# Aldi_Ambiano_Reflow_Oven_Main_Board.net
KiCad netlist of a schematic drawn in EAGLE
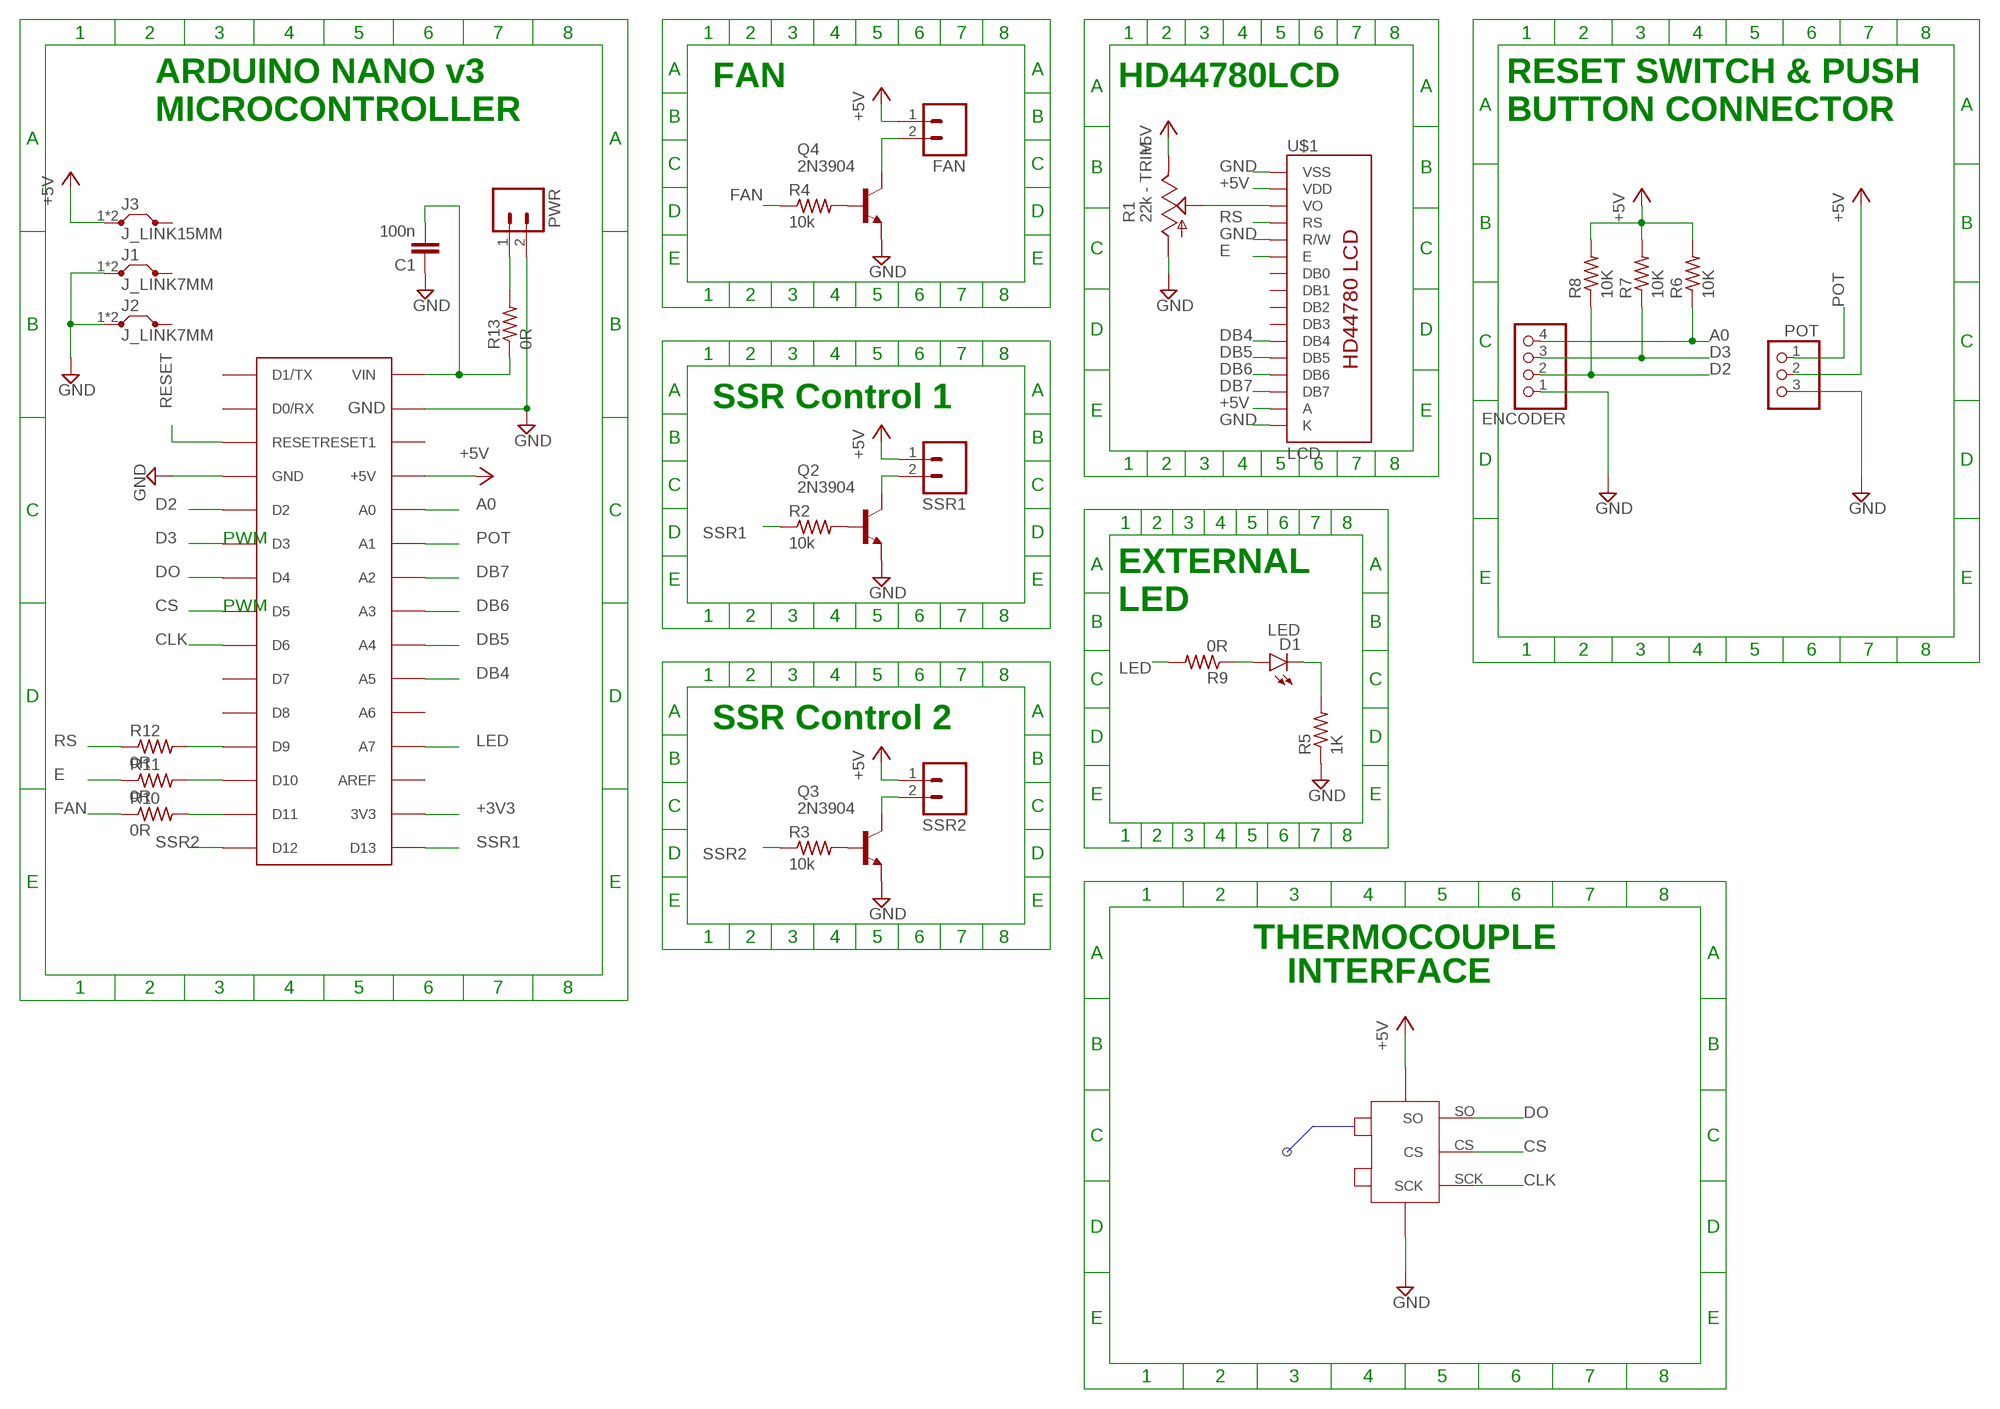
[diagram p0: schematic, sheet 1]

(export (version "E")
  (design (tool "Eeschema 10.0.6"))
  (components
    (comp (ref "ARDUINO")
      (value "Arduino Nano v3.0")
      (footprint "eagle-import:PDIP-32")
      (libsource (lib "eagle-import") (part "ARDUINONANO"))
    )
    (comp (ref "C1")
      (value "100n")
      (footprint "eagle-import:CAP-PTH-5MM")
      (libsource (lib "eagle-import") (part "CAPPTH1"))
    )
    (comp (ref "D1")
      (value "LED")
      (footprint "eagle-import:LED3MM")
      (libsource (lib "eagle-import") (part "LED3MM"))
    )
    (comp (ref "ENCODER")
      (value "PINHD-1X4/90")
      (footprint "eagle-import:1X04_90")
      (libsource (lib "eagle-import") (part "PINHD-1X4/90"))
    )
    (comp (ref "FAN")
      (value "M025MM")
      (footprint "eagle-import:SCREWTERMINAL-5MM-2")
      (libsource (lib "eagle-import") (part "M025MM"))
    )
    (comp (ref "J1")
      (value "J_LINK7MM")
      (footprint "eagle-import:07")
      (libsource (lib "eagle-import") (part "J_LINK7MM"))
    )
    (comp (ref "J2")
      (value "J_LINK7MM")
      (footprint "eagle-import:07")
      (libsource (lib "eagle-import") (part "J_LINK7MM"))
    )
    (comp (ref "J3")
      (value "J_LINK15MM")
      (footprint "eagle-import:15")
      (libsource (lib "eagle-import") (part "J_LINK15MM"))
    )
    (comp (ref "POT")
      (value "PINHD-1X3/90")
      (footprint "eagle-import:1X03_90")
      (libsource (lib "eagle-import") (part "PINHD-1X3/90"))
    )
    (comp (ref "PWR")
      (value "M025MM")
      (footprint "eagle-import:SCREWTERMINAL-5MM-2")
      (libsource (lib "eagle-import") (part "M025MM"))
    )
    (comp (ref "Q2")
      (value "2N3904")
      (footprint "eagle-import:TO92")
      (libsource (lib "eagle-import") (part "2N3904"))
    )
    (comp (ref "Q3")
      (value "2N3904")
      (footprint "eagle-import:TO92")
      (libsource (lib "eagle-import") (part "2N3904"))
    )
    (comp (ref "Q4")
      (value "2N3904")
      (footprint "eagle-import:TO92")
      (libsource (lib "eagle-import") (part "2N3904"))
    )
    (comp (ref "R1")
      (value "22k - TRIM")
      (footprint "eagle-import:CA9V")
      (libsource (lib "eagle-import") (part "TRIM_US-CA9V"))
    )
    (comp (ref "R2")
      (value "10k")
      (footprint "eagle-import:R0207_3")
      (libsource (lib "eagle-import") (part "6MM.3"))
    )
    (comp (ref "R3")
      (value "10k")
      (footprint "eagle-import:R0207_3")
      (libsource (lib "eagle-import") (part "6MM.3"))
    )
    (comp (ref "R4")
      (value "10k")
      (footprint "eagle-import:R0207_3")
      (libsource (lib "eagle-import") (part "6MM.3"))
    )
    (comp (ref "R5")
      (value "1K")
      (footprint "eagle-import:R0207_3")
      (libsource (lib "eagle-import") (part "6MM.3"))
    )
    (comp (ref "R6")
      (value "10K")
      (footprint "eagle-import:R0207_4")
      (libsource (lib "eagle-import") (part "6MM.4"))
    )
    (comp (ref "R7")
      (value "10K")
      (footprint "eagle-import:R0207_3")
      (libsource (lib "eagle-import") (part "6MM.3"))
    )
    (comp (ref "R8")
      (value "10K")
      (footprint "eagle-import:R0207_4")
      (libsource (lib "eagle-import") (part "6MM.4"))
    )
    (comp (ref "R9")
      (value "0R")
      (footprint "eagle-import:R0207_4")
      (libsource (lib "eagle-import") (part "6MM.4"))
    )
    (comp (ref "R10")
      (value "0R")
      (footprint "eagle-import:R0207_3")
      (libsource (lib "eagle-import") (part "6MM.3"))
    )
    (comp (ref "R11")
      (value "0R")
      (footprint "eagle-import:R0207_6")
      (libsource (lib "eagle-import") (part "6MM.6"))
    )
    (comp (ref "R12")
      (value "0R")
      (footprint "eagle-import:R0207_3")
      (libsource (lib "eagle-import") (part "6MM.3"))
    )
    (comp (ref "R13")
      (value "0R")
      (footprint "eagle-import:R0207_5")
      (libsource (lib "eagle-import") (part "6MM.5"))
    )
    (comp (ref "SSR1")
      (value "M025MM")
      (footprint "eagle-import:SCREWTERMINAL-5MM-2")
      (libsource (lib "eagle-import") (part "M025MM"))
    )
    (comp (ref "SSR2")
      (value "M025MM")
      (footprint "eagle-import:SCREWTERMINAL-5MM-2")
      (libsource (lib "eagle-import") (part "M025MM"))
    )
    (comp (ref "U$1")
      (value "LCD")
      (footprint "eagle-import:LCD-16X2-4HOLES")
      (libsource (lib "eagle-import") (part "LCD-HD4478016X2-4-HOLES4-HOLES"))
    )
    (comp (ref "U$2")
      (value "MAX6675_BREAKOUT")
      (footprint "eagle-import:MAX6675_BREAKOUT")
      (libsource (lib "eagle-import") (part "MAX6675_BREAKOUT"))
    )
  )
  (nets
    (net (code "1") (name "+5V") (class "Default")
      (node (ref "ARDUINO") (pin "+5V") (pinfunction "+5V_+5V") (pintype "bidirectional"))
      (node (ref "FAN") (pin "1") (pinfunction "1_1") (pintype "passive"))
      (node (ref "J3") (pin "1") (pinfunction "1_1") (pintype "passive"))
      (node (ref "J3") (pin "2") (pinfunction "1_2") (pintype "passive"))
      (node (ref "POT") (pin "2") (pinfunction "2_2") (pintype "passive"))
      (node (ref "R1") (pin "E") (pinfunction "E_E") (pintype "passive"))
      (node (ref "R6") (pin "2") (pinfunction "2_2") (pintype "passive"))
      (node (ref "R7") (pin "2") (pinfunction "2_2") (pintype "passive"))
      (node (ref "R8") (pin "2") (pinfunction "2_2") (pintype "passive"))
      (node (ref "SSR1") (pin "1") (pinfunction "1_1") (pintype "passive"))
      (node (ref "SSR2") (pin "1") (pinfunction "1_1") (pintype "passive"))
      (node (ref "U$1") (pin "15") (pinfunction "A_15") (pintype "power_in"))
      (node (ref "U$1") (pin "2") (pinfunction "VDD_2") (pintype "power_in"))
      (node (ref "U$2") (pin "VCC") (pinfunction "VCC_VCC") (pintype "power_in"))
    )
    (net (code "2") (name "/+3V3") (class "Default")
      (node (ref "ARDUINO") (pin "3V3") (pinfunction "3V3_3V3") (pintype "bidirectional"))
    )
    (net (code "3") (name "/A0") (class "Default")
      (node (ref "ARDUINO") (pin "A0") (pinfunction "A0_A0") (pintype "bidirectional"))
      (node (ref "ENCODER") (pin "4") (pinfunction "4_4") (pintype "passive"))
      (node (ref "R6") (pin "1") (pinfunction "1_1") (pintype "passive"))
    )
    (net (code "4") (name "/CLK") (class "Default")
      (node (ref "ARDUINO") (pin "D6") (pinfunction "D6_D6") (pintype "bidirectional"))
      (node (ref "U$2") (pin "SCK") (pinfunction "SCK_SCK") (pintype "bidirectional"))
    )
    (net (code "5") (name "/CS") (class "Default")
      (node (ref "ARDUINO") (pin "D5") (pinfunction "D5_D5") (pintype "bidirectional"))
      (node (ref "U$2") (pin "CS") (pinfunction "CS_CS") (pintype "bidirectional"))
    )
    (net (code "6") (name "/D2") (class "Default")
      (node (ref "ARDUINO") (pin "D2") (pinfunction "D2_D2") (pintype "bidirectional"))
      (node (ref "ENCODER") (pin "2") (pinfunction "2_2") (pintype "passive"))
      (node (ref "R8") (pin "1") (pinfunction "1_1") (pintype "passive"))
    )
    (net (code "7") (name "/D3") (class "Default")
      (node (ref "ARDUINO") (pin "D3") (pinfunction "D3_D3") (pintype "bidirectional"))
      (node (ref "ENCODER") (pin "3") (pinfunction "3_3") (pintype "passive"))
      (node (ref "R7") (pin "1") (pinfunction "1_1") (pintype "passive"))
    )
    (net (code "8") (name "/DB4") (class "Default")
      (node (ref "ARDUINO") (pin "A5") (pinfunction "A5_A5") (pintype "bidirectional"))
      (node (ref "U$1") (pin "11") (pinfunction "DB4_11") (pintype "bidirectional"))
    )
    (net (code "9") (name "/DB5") (class "Default")
      (node (ref "ARDUINO") (pin "A4") (pinfunction "A4_A4") (pintype "bidirectional"))
      (node (ref "U$1") (pin "12") (pinfunction "DB5_12") (pintype "bidirectional"))
    )
    (net (code "10") (name "/DB6") (class "Default")
      (node (ref "ARDUINO") (pin "A3") (pinfunction "A3_A3") (pintype "bidirectional"))
      (node (ref "U$1") (pin "13") (pinfunction "DB6_13") (pintype "bidirectional"))
    )
    (net (code "11") (name "/DB7") (class "Default")
      (node (ref "ARDUINO") (pin "A2") (pinfunction "A2_A2") (pintype "bidirectional"))
      (node (ref "U$1") (pin "14") (pinfunction "DB7_14") (pintype "bidirectional"))
    )
    (net (code "12") (name "/DO") (class "Default")
      (node (ref "ARDUINO") (pin "D4") (pinfunction "D4_D4") (pintype "bidirectional"))
      (node (ref "U$2") (pin "SO") (pinfunction "SO_SO") (pintype "bidirectional"))
    )
    (net (code "13") (name "/E") (class "Default")
      (node (ref "R11") (pin "1") (pinfunction "1_1") (pintype "passive"))
      (node (ref "U$1") (pin "6") (pinfunction "E_6") (pintype "input"))
    )
    (net (code "14") (name "/FAN") (class "Default")
      (node (ref "R10") (pin "1") (pinfunction "1_1") (pintype "passive"))
      (node (ref "R4") (pin "1") (pinfunction "1_1") (pintype "passive"))
    )
    (net (code "15") (name "/LED") (class "Default")
      (node (ref "ARDUINO") (pin "A7") (pinfunction "A7_A7") (pintype "bidirectional"))
      (node (ref "R9") (pin "2") (pinfunction "2_2") (pintype "passive"))
    )
    (net (code "16") (name "/POT") (class "Default")
      (node (ref "ARDUINO") (pin "A1") (pinfunction "A1_A1") (pintype "bidirectional"))
      (node (ref "POT") (pin "1") (pinfunction "1_1") (pintype "passive"))
    )
    (net (code "17") (name "/RESET") (class "Default")
      (node (ref "ARDUINO") (pin "RESET") (pinfunction "RESET_RESET") (pintype "bidirectional"))
    )
    (net (code "18") (name "/RS") (class "Default")
      (node (ref "R12") (pin "1") (pinfunction "1_1") (pintype "passive"))
      (node (ref "U$1") (pin "4") (pinfunction "RS_4") (pintype "input"))
    )
    (net (code "19") (name "/SSR1") (class "Default")
      (node (ref "ARDUINO") (pin "D13") (pinfunction "D13_D13") (pintype "bidirectional"))
      (node (ref "R2") (pin "1") (pinfunction "1_1") (pintype "passive"))
    )
    (net (code "20") (name "/SSR2") (class "Default")
      (node (ref "ARDUINO") (pin "D12") (pinfunction "D12_D12") (pintype "bidirectional"))
      (node (ref "R3") (pin "1") (pinfunction "1_1") (pintype "passive"))
    )
    (net (code "21") (name "GND") (class "Default")
      (node (ref "ARDUINO") (pin "GND") (pinfunction "GND_GND") (pintype "bidirectional"))
      (node (ref "ARDUINO") (pin "GND1") (pinfunction "GND_GND1") (pintype "bidirectional"))
      (node (ref "C1") (pin "1") (pinfunction "1_1") (pintype "passive"))
      (node (ref "ENCODER") (pin "1") (pinfunction "1_1") (pintype "passive"))
      (node (ref "J1") (pin "1") (pinfunction "1_1") (pintype "passive"))
      (node (ref "J1") (pin "2") (pinfunction "1_2") (pintype "passive"))
      (node (ref "J2") (pin "1") (pinfunction "1_1") (pintype "passive"))
      (node (ref "J2") (pin "2") (pinfunction "1_2") (pintype "passive"))
      (node (ref "POT") (pin "3") (pinfunction "3_3") (pintype "passive"))
      (node (ref "PWR") (pin "2") (pinfunction "2_2") (pintype "passive"))
      (node (ref "Q2") (pin "3") (pinfunction "E_3") (pintype "passive"))
      (node (ref "Q3") (pin "3") (pinfunction "E_3") (pintype "passive"))
      (node (ref "Q4") (pin "3") (pinfunction "E_3") (pintype "passive"))
      (node (ref "R1") (pin "A") (pinfunction "A_A") (pintype "passive"))
      (node (ref "R5") (pin "1") (pinfunction "1_1") (pintype "passive"))
      (node (ref "U$1") (pin "1") (pinfunction "VSS_1") (pintype "power_in"))
      (node (ref "U$1") (pin "16") (pinfunction "K_16") (pintype "power_in"))
      (node (ref "U$1") (pin "5") (pinfunction "R/W_5") (pintype "input"))
      (node (ref "U$2") (pin "GND") (pinfunction "GND_GND") (pintype "power_in"))
    )
    (net (code "22") (name "Net-(ARDUINO-PadD9)") (class "Default")
      (node (ref "ARDUINO") (pin "D9") (pinfunction "D9_D9") (pintype "bidirectional"))
      (node (ref "R12") (pin "2") (pinfunction "2_2") (pintype "passive"))
    )
    (net (code "23") (name "Net-(ARDUINO-PadD10)") (class "Default")
      (node (ref "ARDUINO") (pin "D10") (pinfunction "D10_D10") (pintype "bidirectional"))
      (node (ref "R11") (pin "2") (pinfunction "2_2") (pintype "passive"))
    )
    (net (code "24") (name "Net-(ARDUINO-PadD11)") (class "Default")
      (node (ref "ARDUINO") (pin "D11") (pinfunction "D11_D11") (pintype "bidirectional"))
      (node (ref "R10") (pin "2") (pinfunction "2_2") (pintype "passive"))
    )
    (net (code "25") (name "Net-(ARDUINO-PadVIN)") (class "Default")
      (node (ref "ARDUINO") (pin "VIN") (pinfunction "VIN_VIN") (pintype "bidirectional"))
      (node (ref "C1") (pin "2") (pinfunction "2_2") (pintype "passive"))
      (node (ref "R13") (pin "1") (pinfunction "1_1") (pintype "passive"))
    )
    (net (code "26") (name "Net-(D1-C)") (class "Default")
      (node (ref "D1") (pin "K") (pinfunction "C_K") (pintype "passive"))
      (node (ref "R5") (pin "2") (pinfunction "2_2") (pintype "passive"))
    )
    (net (code "27") (name "Net-(D1-PadA)") (class "Default")
      (node (ref "D1") (pin "A") (pinfunction "A_A") (pintype "passive"))
      (node (ref "R9") (pin "1") (pinfunction "1_1") (pintype "passive"))
    )
    (net (code "28") (name "Net-(PWR-Pad1)") (class "Default")
      (node (ref "PWR") (pin "1") (pinfunction "1_1") (pintype "passive"))
      (node (ref "R13") (pin "2") (pinfunction "2_2") (pintype "passive"))
    )
    (net (code "29") (name "Net-(Q2-B)") (class "Default")
      (node (ref "Q2") (pin "2") (pinfunction "B_2") (pintype "passive"))
      (node (ref "R2") (pin "2") (pinfunction "2_2") (pintype "passive"))
    )
    (net (code "30") (name "Net-(Q2-C)") (class "Default")
      (node (ref "Q2") (pin "1") (pinfunction "C_1") (pintype "passive"))
      (node (ref "SSR1") (pin "2") (pinfunction "2_2") (pintype "passive"))
    )
    (net (code "31") (name "Net-(Q3-B)") (class "Default")
      (node (ref "Q3") (pin "2") (pinfunction "B_2") (pintype "passive"))
      (node (ref "R3") (pin "2") (pinfunction "2_2") (pintype "passive"))
    )
    (net (code "32") (name "Net-(Q3-C)") (class "Default")
      (node (ref "Q3") (pin "1") (pinfunction "C_1") (pintype "passive"))
      (node (ref "SSR2") (pin "2") (pinfunction "2_2") (pintype "passive"))
    )
    (net (code "33") (name "Net-(Q4-B)") (class "Default")
      (node (ref "Q4") (pin "2") (pinfunction "B_2") (pintype "passive"))
      (node (ref "R4") (pin "2") (pinfunction "2_2") (pintype "passive"))
    )
    (net (code "34") (name "Net-(Q4-C)") (class "Default")
      (node (ref "FAN") (pin "2") (pinfunction "2_2") (pintype "passive"))
      (node (ref "Q4") (pin "1") (pinfunction "C_1") (pintype "passive"))
    )
    (net (code "35") (name "Net-(U$1-VO)") (class "Default")
      (node (ref "R1") (pin "S") (pinfunction "S_S") (pintype "passive"))
      (node (ref "U$1") (pin "3") (pinfunction "VO_3") (pintype "bidirectional"))
    )
    (net (code "36") (name "unconnected-(ARDUINO-PadA6)") (class "Default")
      (node (ref "ARDUINO") (pin "A6") (pinfunction "A6_A6") (pintype "bidirectional"))
    )
    (net (code "37") (name "unconnected-(ARDUINO-PadAREF)") (class "Default")
      (node (ref "ARDUINO") (pin "AREF") (pinfunction "AREF_AREF") (pintype "bidirectional"))
    )
    (net (code "38") (name "unconnected-(ARDUINO-PadD0{slash}RX)") (class "Default")
      (node (ref "ARDUINO") (pin "D0/RX") (pinfunction "D0/RX_D0/RX") (pintype "bidirectional"))
    )
    (net (code "39") (name "unconnected-(ARDUINO-PadD1{slash}TX)") (class "Default")
      (node (ref "ARDUINO") (pin "D1/TX") (pinfunction "D1/TX_D1/TX") (pintype "bidirectional"))
    )
    (net (code "40") (name "unconnected-(ARDUINO-PadD7)") (class "Default")
      (node (ref "ARDUINO") (pin "D7") (pinfunction "D7_D7") (pintype "bidirectional"))
    )
    (net (code "41") (name "unconnected-(ARDUINO-PadD8)") (class "Default")
      (node (ref "ARDUINO") (pin "D8") (pinfunction "D8_D8") (pintype "bidirectional"))
    )
    (net (code "42") (name "unconnected-(ARDUINO-PadRESET1)") (class "Default")
      (node (ref "ARDUINO") (pin "RESET1") (pinfunction "RESET1_RESET1") (pintype "bidirectional"))
    )
    (net (code "43") (name "unconnected-(U$1-DB0-Pad7)") (class "Default")
      (node (ref "U$1") (pin "7") (pinfunction "DB0_7") (pintype "bidirectional"))
    )
    (net (code "44") (name "unconnected-(U$1-DB1-Pad8)") (class "Default")
      (node (ref "U$1") (pin "8") (pinfunction "DB1_8") (pintype "bidirectional"))
    )
    (net (code "45") (name "unconnected-(U$1-DB2-Pad9)") (class "Default")
      (node (ref "U$1") (pin "9") (pinfunction "DB2_9") (pintype "bidirectional"))
    )
    (net (code "46") (name "unconnected-(U$1-DB3-Pad10)") (class "Default")
      (node (ref "U$1") (pin "10") (pinfunction "DB3_10") (pintype "bidirectional"))
    )
  )
)
